# apollo-ctrl.net
KiCad netlist of a schematic drawn in EAGLE
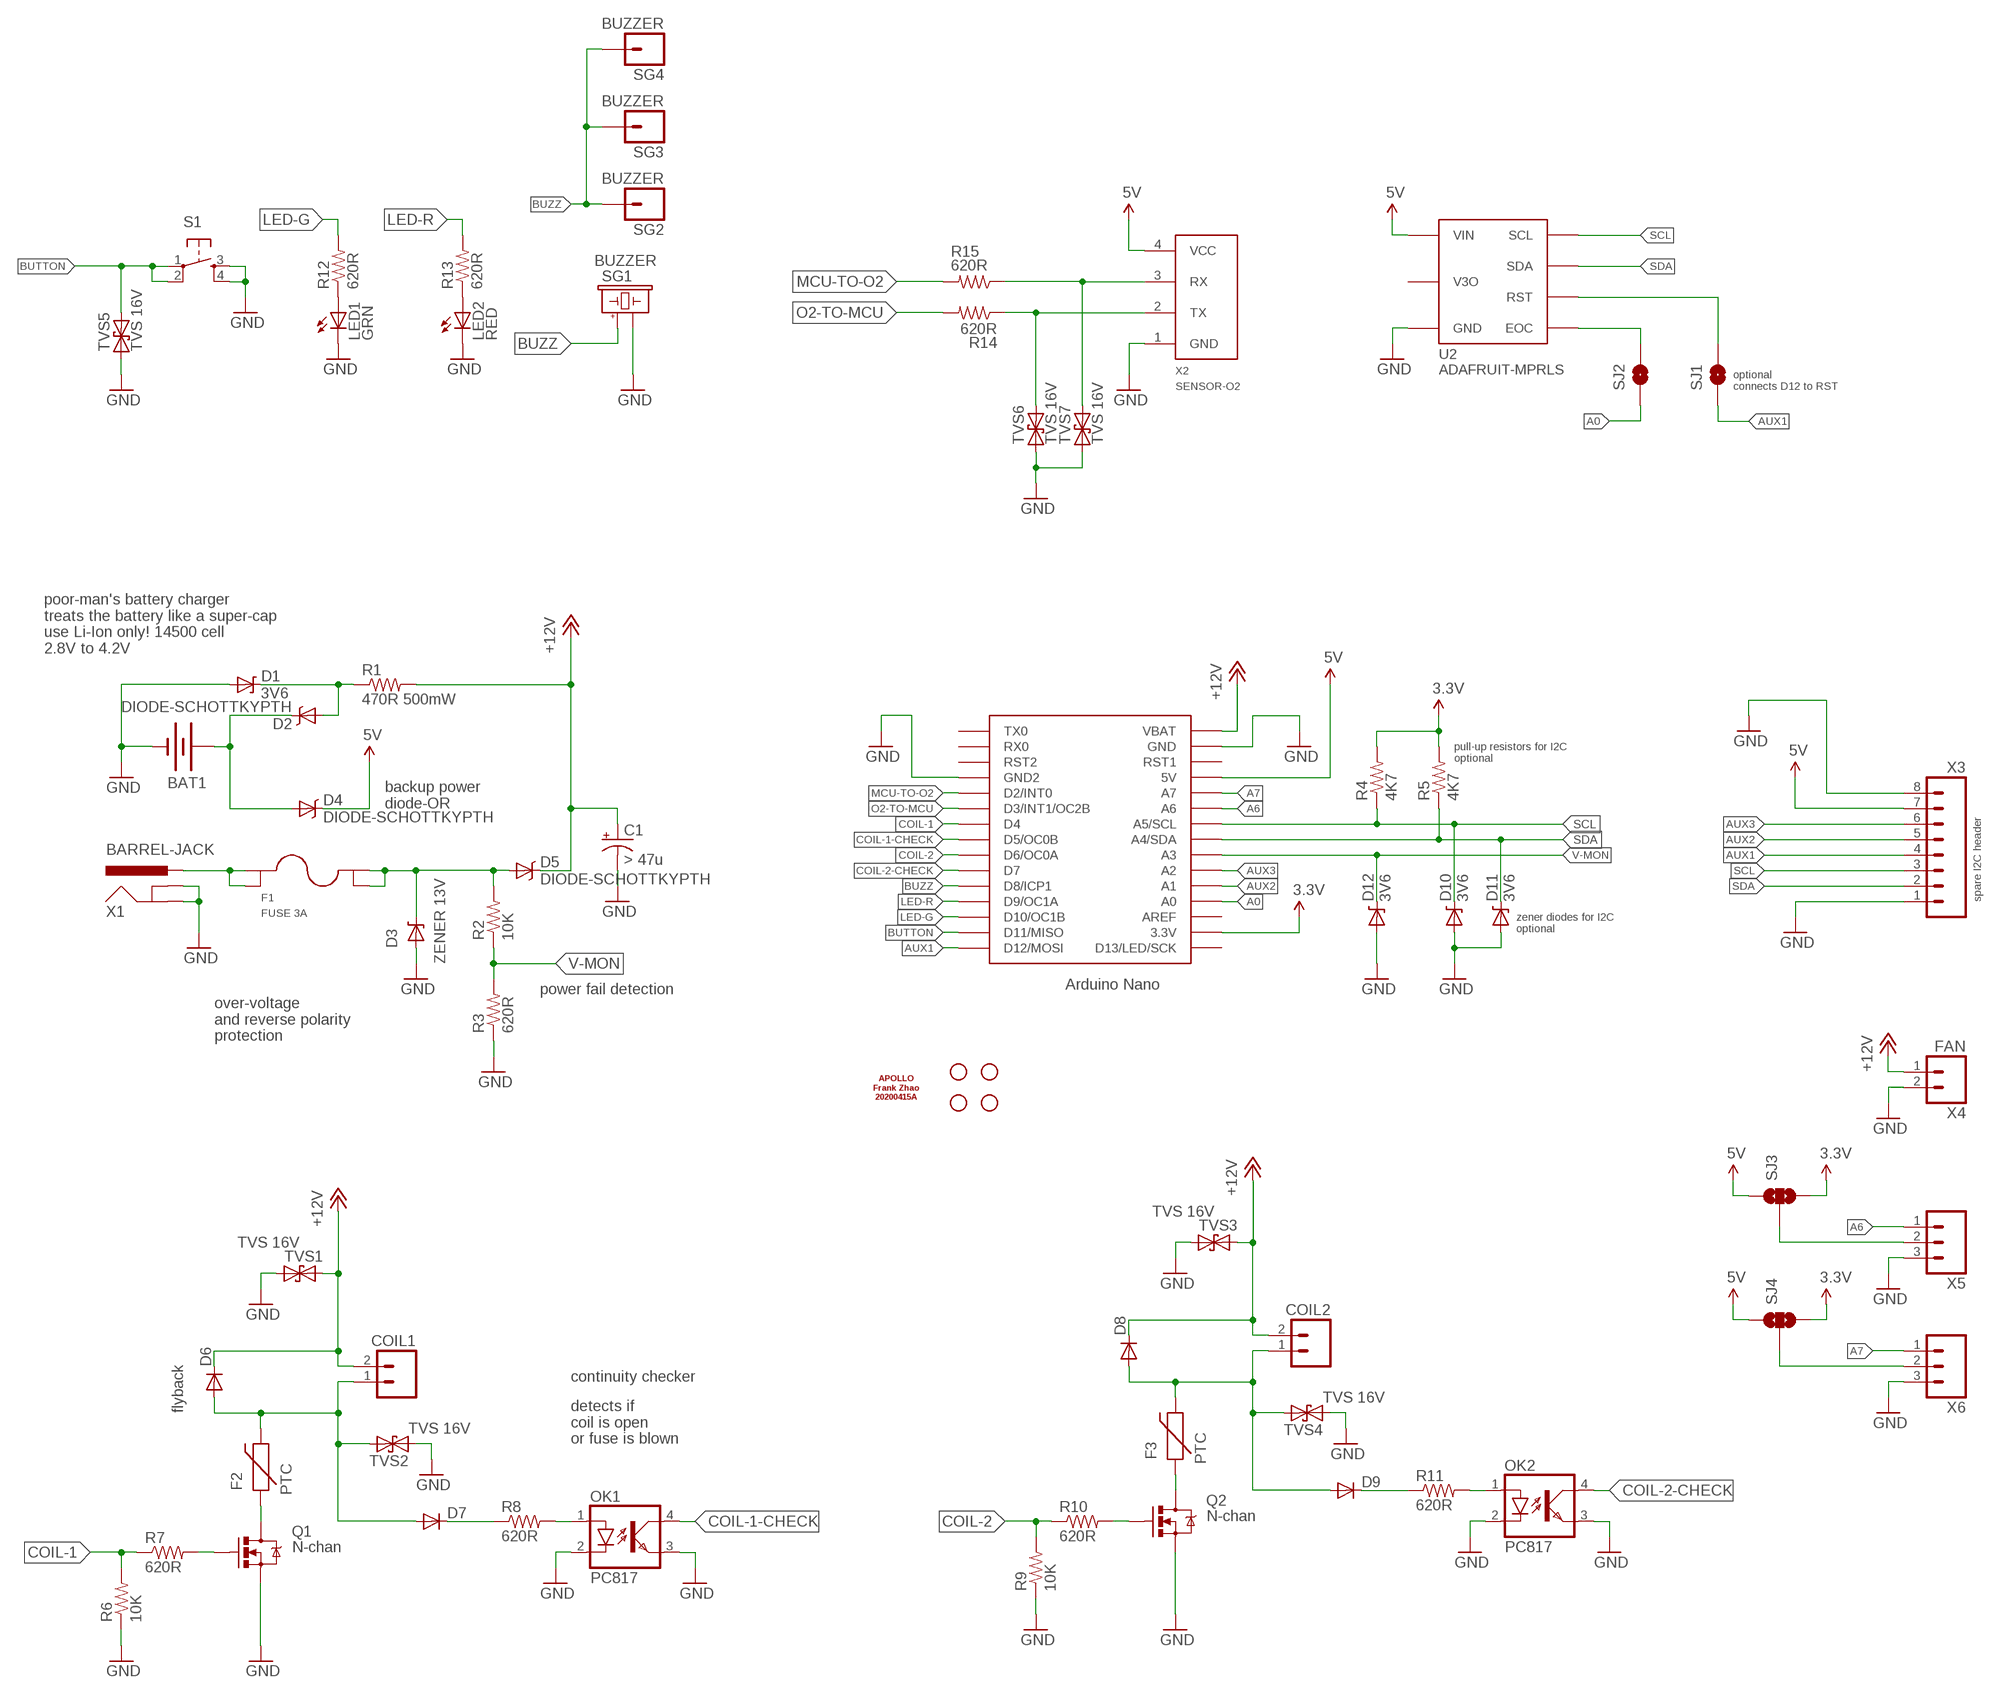
[diagram p0: schematic, sheet 1]

(export (version "E")
  (design (tool "Eeschema 10.0.6"))
  (components
    (comp (ref "BAT1")
      (value "BATTERYAA-KIT")
      (footprint "eagle-import:BATTERY-AA-KIT")
      (libsource (lib "eagle-import") (part "BATTERYAA-KIT"))
    )
    (comp (ref "C1")
      (value "> 47u")
      (footprint "eagle-import:CPOL-RADIAL-1000UF-25V")
      (libsource (lib "eagle-import") (part "CAP_POLPTH4"))
    )
    (comp (ref "COIL1")
      (value "M023.5MM")
      (footprint "eagle-import:SCREWTERMINAL-3.5MM-2")
      (libsource (lib "eagle-import") (part "M023.5MM"))
    )
    (comp (ref "COIL2")
      (value "M023.5MM")
      (footprint "eagle-import:SCREWTERMINAL-3.5MM-2")
      (libsource (lib "eagle-import") (part "M023.5MM"))
    )
    (comp (ref "D1")
      (value "3V6")
      (footprint "eagle-import:DIODE-1N4148")
      (libsource (lib "eagle-import") (part "DIODE-ZENER1N4148"))
    )
    (comp (ref "D2")
      (value "DIODE-SCHOTTKYPTH")
      (footprint "eagle-import:DIODE-1N4001")
      (libsource (lib "eagle-import") (part "DIODE-SCHOTTKYPTH"))
    )
    (comp (ref "D3")
      (value "ZENER 13V")
      (footprint "eagle-import:DO201-15")
      (libsource (lib "eagle-import") (part "DIODE-ZENER-DO201-15"))
    )
    (comp (ref "D4")
      (value "DIODE-SCHOTTKYPTH")
      (footprint "eagle-import:DIODE-1N4001")
      (libsource (lib "eagle-import") (part "DIODE-SCHOTTKYPTH"))
    )
    (comp (ref "D5")
      (value "DIODE-SCHOTTKYPTH")
      (footprint "eagle-import:DIODE-1N4001")
      (libsource (lib "eagle-import") (part "DIODE-SCHOTTKYPTH"))
    )
    (comp (ref "D6")
      (value "DIODE1N4148")
      (footprint "eagle-import:DIODE-1N4148")
      (libsource (lib "eagle-import") (part "DIODE1N4148"))
    )
    (comp (ref "D7")
      (value "DIODE1N4148")
      (footprint "eagle-import:DIODE-1N4148")
      (libsource (lib "eagle-import") (part "DIODE1N4148"))
    )
    (comp (ref "D8")
      (value "DIODE1N4148")
      (footprint "eagle-import:DIODE-1N4148")
      (libsource (lib "eagle-import") (part "DIODE1N4148"))
    )
    (comp (ref "D9")
      (value "DIODE1N4148")
      (footprint "eagle-import:DIODE-1N4148")
      (libsource (lib "eagle-import") (part "DIODE1N4148"))
    )
    (comp (ref "D10")
      (value "3V6")
      (footprint "eagle-import:DIODE-1N4148")
      (libsource (lib "eagle-import") (part "DIODE-ZENER1N4148"))
    )
    (comp (ref "D11")
      (value "3V6")
      (footprint "eagle-import:DIODE-1N4148")
      (libsource (lib "eagle-import") (part "DIODE-ZENER1N4148"))
    )
    (comp (ref "D12")
      (value "3V6")
      (footprint "eagle-import:DIODE-1N4148")
      (libsource (lib "eagle-import") (part "DIODE-ZENER1N4148"))
    )
    (comp (ref "F1")
      (value "FUSE 3A")
      (footprint "eagle-import:FUSE-KEYSTONE-3568")
      (libsource (lib "eagle-import") (part "FUSE-4PIN-KEYSTONE-3568"))
    )
    (comp (ref "F2")
      (value "PTC")
      (footprint "eagle-import:PTC")
      (libsource (lib "eagle-import") (part "PTCPTH"))
    )
    (comp (ref "F3")
      (value "PTC")
      (footprint "eagle-import:PTC")
      (libsource (lib "eagle-import") (part "PTCPTH"))
    )
    (comp (ref "JP1")
      (value "STAND-OFF")
      (footprint "eagle-import:STAND-OFF")
      (libsource (lib "eagle-import") (part "STAND-OFF"))
    )
    (comp (ref "JP2")
      (value "STAND-OFF")
      (footprint "eagle-import:STAND-OFF")
      (libsource (lib "eagle-import") (part "STAND-OFF"))
    )
    (comp (ref "JP3")
      (value "STAND-OFF")
      (footprint "eagle-import:STAND-OFF")
      (libsource (lib "eagle-import") (part "STAND-OFF"))
    )
    (comp (ref "JP4")
      (value "STAND-OFF")
      (footprint "eagle-import:STAND-OFF")
      (libsource (lib "eagle-import") (part "STAND-OFF"))
    )
    (comp (ref "LED1")
      (value "GRN")
      (footprint "eagle-import:LED5MM")
      (libsource (lib "eagle-import") (part "LED5MM"))
    )
    (comp (ref "LED2")
      (value "RED")
      (footprint "eagle-import:LED5MM")
      (libsource (lib "eagle-import") (part "LED5MM"))
    )
    (comp (ref "LOGO1")
      (value "APOLLO-LOGO")
      (footprint "eagle-import:APOLLO-LOGO")
      (libsource (lib "eagle-import") (part "APOLLO-LOGO"))
    )
    (comp (ref "OK1")
      (value "PC817")
      (footprint "eagle-import:DIL04")
      (fields (field (name "MPN") "PC817X4J000F"))
      (libsource (lib "eagle-import") (part "PC817"))
    )
    (comp (ref "OK2")
      (value "PC817")
      (footprint "eagle-import:DIL04")
      (fields (field (name "MPN") "PC817X4J000F"))
      (libsource (lib "eagle-import") (part "PC817"))
    )
    (comp (ref "Q1")
      (value "N-chan")
      (footprint "eagle-import:TO220V")
      (libsource (lib "eagle-import") (part "MOSFET-NCHANNELPTH2"))
    )
    (comp (ref "Q2")
      (value "N-chan")
      (footprint "eagle-import:TO220V")
      (libsource (lib "eagle-import") (part "MOSFET-NCHANNELPTH2"))
    )
    (comp (ref "R1")
      (value "470R 500mW")
      (footprint "eagle-import:AXIAL-0.5")
      (libsource (lib "eagle-import") (part "RESISTORPTH-1/2W"))
    )
    (comp (ref "R2")
      (value "10K")
      (footprint "eagle-import:AXIAL-0.4")
      (libsource (lib "eagle-import") (part "RESISTORPTH-1/4W"))
    )
    (comp (ref "R3")
      (value "620R")
      (footprint "eagle-import:AXIAL-0.4")
      (libsource (lib "eagle-import") (part "RESISTORPTH-1/4W"))
    )
    (comp (ref "R4")
      (value "4K7")
      (footprint "eagle-import:AXIAL-0.4")
      (libsource (lib "eagle-import") (part "RESISTORPTH-1/4W"))
    )
    (comp (ref "R5")
      (value "4K7")
      (footprint "eagle-import:AXIAL-0.4")
      (libsource (lib "eagle-import") (part "RESISTORPTH-1/4W"))
    )
    (comp (ref "R6")
      (value "10K")
      (footprint "eagle-import:AXIAL-0.4")
      (libsource (lib "eagle-import") (part "RESISTORPTH-1/4W"))
    )
    (comp (ref "R7")
      (value "620R")
      (footprint "eagle-import:AXIAL-0.4")
      (libsource (lib "eagle-import") (part "RESISTORPTH-1/4W"))
    )
    (comp (ref "R8")
      (value "620R")
      (footprint "eagle-import:AXIAL-0.4")
      (libsource (lib "eagle-import") (part "RESISTORPTH-1/4W"))
    )
    (comp (ref "R9")
      (value "10K")
      (footprint "eagle-import:AXIAL-0.4")
      (libsource (lib "eagle-import") (part "RESISTORPTH-1/4W"))
    )
    (comp (ref "R10")
      (value "620R")
      (footprint "eagle-import:AXIAL-0.4")
      (libsource (lib "eagle-import") (part "RESISTORPTH-1/4W"))
    )
    (comp (ref "R11")
      (value "620R")
      (footprint "eagle-import:AXIAL-0.4")
      (libsource (lib "eagle-import") (part "RESISTORPTH-1/4W"))
    )
    (comp (ref "R12")
      (value "620R")
      (footprint "eagle-import:AXIAL-0.4")
      (libsource (lib "eagle-import") (part "RESISTORPTH-1/4W"))
    )
    (comp (ref "R13")
      (value "620R")
      (footprint "eagle-import:AXIAL-0.4")
      (libsource (lib "eagle-import") (part "RESISTORPTH-1/4W"))
    )
    (comp (ref "R14")
      (value "620R")
      (footprint "eagle-import:AXIAL-0.4")
      (libsource (lib "eagle-import") (part "RESISTORPTH-1/4W"))
    )
    (comp (ref "R15")
      (value "620R")
      (footprint "eagle-import:AXIAL-0.4")
      (libsource (lib "eagle-import") (part "RESISTORPTH-1/4W"))
    )
    (comp (ref "S1")
      (value "TAC_SWITCHPTH")
      (footprint "eagle-import:TACTILE-PTH")
      (libsource (lib "eagle-import") (part "TAC_SWITCHPTH"))
    )
    (comp (ref "SG1")
      (value "BUZZER")
      (footprint "eagle-import:BUZZER-AI-3035")
      (libsource (lib "eagle-import") (part "BUZZER-POL-AI-3035"))
    )
    (comp (ref "SG2")
      (value "BUZZER")
      (footprint "eagle-import:1X01NS")
      (libsource (lib "eagle-import") (part "M01-TH-NS"))
    )
    (comp (ref "SG3")
      (value "BUZZER")
      (footprint "eagle-import:1X01NS")
      (libsource (lib "eagle-import") (part "M01-TH-NS"))
    )
    (comp (ref "SG4")
      (value "BUZZER")
      (footprint "eagle-import:1X01NS")
      (libsource (lib "eagle-import") (part "M01-TH-NS"))
    )
    (comp (ref "SJ1")
      (value "SOLDERJUMPERNO")
      (footprint "eagle-import:SJ_2S-NO")
      (libsource (lib "eagle-import") (part "SOLDERJUMPERNO"))
    )
    (comp (ref "SJ2")
      (value "SOLDERJUMPERNO")
      (footprint "eagle-import:SJ_2S-NO")
      (libsource (lib "eagle-import") (part "SOLDERJUMPERNO"))
    )
    (comp (ref "SJ3")
      (value "SOLDERJUMPER_2WAYS")
      (footprint "eagle-import:SJ_3")
      (libsource (lib "eagle-import") (part "SOLDERJUMPER_2WAYS"))
    )
    (comp (ref "SJ4")
      (value "SOLDERJUMPER_2WAYS")
      (footprint "eagle-import:SJ_3")
      (libsource (lib "eagle-import") (part "SOLDERJUMPER_2WAYS"))
    )
    (comp (ref "TVS1")
      (value "TVS 16V")
      (footprint "eagle-import:DIODE-1N4148")
      (libsource (lib "eagle-import") (part "TVS1N4148"))
    )
    (comp (ref "TVS2")
      (value "TVS 16V")
      (footprint "eagle-import:DIODE-1N4148")
      (libsource (lib "eagle-import") (part "TVS1N4148"))
    )
    (comp (ref "TVS3")
      (value "TVS 16V")
      (footprint "eagle-import:DIODE-1N4148")
      (libsource (lib "eagle-import") (part "TVS1N4148"))
    )
    (comp (ref "TVS4")
      (value "TVS 16V")
      (footprint "eagle-import:DIODE-1N4148")
      (libsource (lib "eagle-import") (part "TVS1N4148"))
    )
    (comp (ref "TVS5")
      (value "TVS 16V")
      (footprint "eagle-import:DIODE-1N4148")
      (libsource (lib "eagle-import") (part "TVS1N4148"))
    )
    (comp (ref "TVS6")
      (value "TVS 16V")
      (footprint "eagle-import:DIODE-1N4148")
      (libsource (lib "eagle-import") (part "TVS1N4148"))
    )
    (comp (ref "TVS7")
      (value "TVS 16V")
      (footprint "eagle-import:DIODE-1N4148")
      (libsource (lib "eagle-import") (part "TVS1N4148"))
    )
    (comp (ref "U1")
      (value "NANO")
      (footprint "eagle-import:NANO")
      (libsource (lib "eagle-import") (part "NANO"))
    )
    (comp (ref "U2")
      (value "ADAFRUIT-MPRLS")
      (footprint "eagle-import:ADAFRUIT-MPRLS")
      (libsource (lib "eagle-import") (part "ADAFRUIT-MPRLS-W-HOLES"))
    )
    (comp (ref "X1")
      (value "BARREL-JACK")
      (footprint "eagle-import:POWER_JACK_PTH")
      (libsource (lib "eagle-import") (part "POWER_JACKPTH"))
    )
    (comp (ref "X2")
      (value "SENSOR-O2")
      (footprint "eagle-import:JST-PH-4-VERT")
      (libsource (lib "eagle-import") (part "SENSOR-O2-JST-VERT"))
    )
    (comp (ref "X3")
      (value "M081X08")
      (footprint "eagle-import:1X08")
      (libsource (lib "eagle-import") (part "M081X08"))
    )
    (comp (ref "X4")
      (value "FAN")
      (footprint "eagle-import:1X02")
      (libsource (lib "eagle-import") (part "M02PTH"))
    )
    (comp (ref "X5")
      (value "M03PTH")
      (footprint "eagle-import:1X03")
      (libsource (lib "eagle-import") (part "M03PTH"))
    )
    (comp (ref "X6")
      (value "M03PTH")
      (footprint "eagle-import:1X03")
      (libsource (lib "eagle-import") (part "M03PTH"))
    )
  )
  (nets
    (net (code "1") (name "+12V") (class "Default")
      (node (ref "C1") (pin "1") (pinfunction "+_1") (pintype "passive"))
      (node (ref "COIL1") (pin "2") (pinfunction "2_2") (pintype "passive"))
      (node (ref "COIL2") (pin "2") (pinfunction "2_2") (pintype "passive"))
      (node (ref "D5") (pin "C") (pinfunction "C_C") (pintype "passive"))
      (node (ref "D6") (pin "C") (pinfunction "C_C") (pintype "passive"))
      (node (ref "D8") (pin "C") (pinfunction "C_C") (pintype "passive"))
      (node (ref "R1") (pin "P$2") (pinfunction "2_P$2") (pintype "passive"))
      (node (ref "TVS1") (pin "C") (pinfunction "C_C") (pintype "passive"))
      (node (ref "TVS3") (pin "C") (pinfunction "C_C") (pintype "passive"))
      (node (ref "U1") (pin "RAW") (pinfunction "VBAT_RAW") (pintype "bidirectional"))
      (node (ref "X4") (pin "1") (pinfunction "1_1") (pintype "passive"))
    )
    (net (code "2") (name "3.3V") (class "Default")
      (node (ref "R4") (pin "P$2") (pinfunction "2_P$2") (pintype "passive"))
      (node (ref "R5") (pin "P$2") (pinfunction "2_P$2") (pintype "passive"))
      (node (ref "SJ3") (pin "3") (pinfunction "3_3") (pintype "passive"))
      (node (ref "SJ4") (pin "3") (pinfunction "3_3") (pintype "passive"))
      (node (ref "U1") (pin "3.3V") (pinfunction "3.3V_3.3V") (pintype "bidirectional"))
    )
    (net (code "3") (name "5V") (class "Default")
      (node (ref "D4") (pin "C") (pinfunction "C_C") (pintype "passive"))
      (node (ref "SJ3") (pin "1") (pinfunction "1_1") (pintype "passive"))
      (node (ref "SJ4") (pin "1") (pinfunction "1_1") (pintype "passive"))
      (node (ref "U1") (pin "5V") (pinfunction "5V_5V") (pintype "bidirectional"))
      (node (ref "U2") (pin "VIN") (pinfunction "VIN_VIN") (pintype "input"))
      (node (ref "X2") (pin "4") (pinfunction "VCC_4") (pintype "input"))
      (node (ref "X3") (pin "7") (pinfunction "7_7") (pintype "passive"))
    )
    (net (code "4") (name "A0") (class "Default")
      (node (ref "SJ2") (pin "1") (pinfunction "1_1") (pintype "passive"))
      (node (ref "U1") (pin "A0") (pinfunction "A0_A0") (pintype "bidirectional"))
    )
    (net (code "5") (name "A6") (class "Default")
      (node (ref "U1") (pin "A6") (pinfunction "A6_A6") (pintype "bidirectional"))
      (node (ref "X5") (pin "1") (pinfunction "1_1") (pintype "passive"))
    )
    (net (code "6") (name "A7") (class "Default")
      (node (ref "U1") (pin "A7") (pinfunction "A7_A7") (pintype "bidirectional"))
      (node (ref "X6") (pin "1") (pinfunction "1_1") (pintype "passive"))
    )
    (net (code "7") (name "AUX1") (class "Default")
      (node (ref "SJ1") (pin "1") (pinfunction "1_1") (pintype "passive"))
      (node (ref "U1") (pin "D12") (pinfunction "D12/MOSI_D12") (pintype "bidirectional"))
      (node (ref "X3") (pin "4") (pinfunction "4_4") (pintype "passive"))
    )
    (net (code "8") (name "AUX2") (class "Default")
      (node (ref "U1") (pin "A1") (pinfunction "A1_A1") (pintype "bidirectional"))
      (node (ref "X3") (pin "5") (pinfunction "5_5") (pintype "passive"))
    )
    (net (code "9") (name "AUX3") (class "Default")
      (node (ref "U1") (pin "A2") (pinfunction "A2_A2") (pintype "bidirectional"))
      (node (ref "X3") (pin "6") (pinfunction "6_6") (pintype "passive"))
    )
    (net (code "10") (name "BUTTON") (class "Default")
      (node (ref "S1") (pin "1") (pinfunction "1_1") (pintype "passive"))
      (node (ref "S1") (pin "2") (pinfunction "2_2") (pintype "passive"))
      (node (ref "TVS5") (pin "C") (pinfunction "C_C") (pintype "passive"))
      (node (ref "U1") (pin "D11") (pinfunction "D11/MISO_D11") (pintype "bidirectional"))
    )
    (net (code "11") (name "BUZZ") (class "Default")
      (node (ref "SG1") (pin "P") (pinfunction "P_P") (pintype "passive"))
      (node (ref "SG2") (pin "1") (pinfunction "1_1") (pintype "passive"))
      (node (ref "SG3") (pin "1") (pinfunction "1_1") (pintype "passive"))
      (node (ref "SG4") (pin "1") (pinfunction "1_1") (pintype "passive"))
      (node (ref "U1") (pin "D8") (pinfunction "D8/ICP1_D8") (pintype "bidirectional"))
    )
    (net (code "12") (name "COIL-1") (class "Default")
      (node (ref "R6") (pin "P$2") (pinfunction "2_P$2") (pintype "passive"))
      (node (ref "R7") (pin "P$1") (pinfunction "1_P$1") (pintype "passive"))
      (node (ref "U1") (pin "D4") (pinfunction "D4_D4") (pintype "bidirectional"))
    )
    (net (code "13") (name "COIL-1-CHECK") (class "Default")
      (node (ref "OK1") (pin "4") (pinfunction "COL_4") (pintype "passive"))
      (node (ref "U1") (pin "D5") (pinfunction "D5/OC0B_D5") (pintype "bidirectional"))
    )
    (net (code "14") (name "COIL-2") (class "Default")
      (node (ref "R10") (pin "P$1") (pinfunction "1_P$1") (pintype "passive"))
      (node (ref "R9") (pin "P$2") (pinfunction "2_P$2") (pintype "passive"))
      (node (ref "U1") (pin "D6") (pinfunction "D6/OC0A_D6") (pintype "bidirectional"))
    )
    (net (code "15") (name "COIL-2-CHECK") (class "Default")
      (node (ref "OK2") (pin "4") (pinfunction "COL_4") (pintype "passive"))
      (node (ref "U1") (pin "D7") (pinfunction "D7_D7") (pintype "bidirectional"))
    )
    (net (code "16") (name "GND") (class "Default")
      (node (ref "BAT1") (pin "GND@1") (pinfunction "-_GND@1") (pintype "power_in"))
      (node (ref "C1") (pin "2") (pinfunction "-_2") (pintype "passive"))
      (node (ref "D1") (pin "A") (pinfunction "A_A") (pintype "passive"))
      (node (ref "D10") (pin "A") (pinfunction "A_A") (pintype "passive"))
      (node (ref "D11") (pin "A") (pinfunction "A_A") (pintype "passive"))
      (node (ref "D12") (pin "A") (pinfunction "A_A") (pintype "passive"))
      (node (ref "D3") (pin "A") (pinfunction "A_A") (pintype "passive"))
      (node (ref "LED1") (pin "K") (pinfunction "C_K") (pintype "passive"))
      (node (ref "LED2") (pin "K") (pinfunction "C_K") (pintype "passive"))
      (node (ref "OK1") (pin "2") (pinfunction "C_2") (pintype "passive"))
      (node (ref "OK1") (pin "3") (pinfunction "EMIT_3") (pintype "passive"))
      (node (ref "OK2") (pin "2") (pinfunction "C_2") (pintype "passive"))
      (node (ref "OK2") (pin "3") (pinfunction "EMIT_3") (pintype "passive"))
      (node (ref "Q1") (pin "3") (pinfunction "S_3") (pintype "passive"))
      (node (ref "Q2") (pin "3") (pinfunction "S_3") (pintype "passive"))
      (node (ref "R3") (pin "P$1") (pinfunction "1_P$1") (pintype "passive"))
      (node (ref "R6") (pin "P$1") (pinfunction "1_P$1") (pintype "passive"))
      (node (ref "R9") (pin "P$1") (pinfunction "1_P$1") (pintype "passive"))
      (node (ref "S1") (pin "3") (pinfunction "3_3") (pintype "passive"))
      (node (ref "S1") (pin "4") (pinfunction "4_4") (pintype "passive"))
      (node (ref "SG1") (pin "N") (pinfunction "N_N") (pintype "passive"))
      (node (ref "TVS1") (pin "A") (pinfunction "A_A") (pintype "passive"))
      (node (ref "TVS2") (pin "A") (pinfunction "A_A") (pintype "passive"))
      (node (ref "TVS3") (pin "A") (pinfunction "A_A") (pintype "passive"))
      (node (ref "TVS4") (pin "A") (pinfunction "A_A") (pintype "passive"))
      (node (ref "TVS5") (pin "A") (pinfunction "A_A") (pintype "passive"))
      (node (ref "TVS6") (pin "A") (pinfunction "A_A") (pintype "passive"))
      (node (ref "TVS7") (pin "A") (pinfunction "A_A") (pintype "passive"))
      (node (ref "U1") (pin "GND") (pinfunction "GND_GND") (pintype "bidirectional"))
      (node (ref "U1") (pin "GND1") (pinfunction "GND2_GND1") (pintype "bidirectional"))
      (node (ref "U2") (pin "GND") (pinfunction "GND_GND") (pintype "input"))
      (node (ref "X1") (pin "GND") (pinfunction "GND_GND") (pintype "bidirectional"))
      (node (ref "X1") (pin "GNDBREAK") (pinfunction "GNDBREAK_GNDBREAK") (pintype "bidirectional"))
      (node (ref "X2") (pin "1") (pinfunction "GND_1") (pintype "input"))
      (node (ref "X3") (pin "1") (pinfunction "1_1") (pintype "passive"))
      (node (ref "X3") (pin "8") (pinfunction "8_8") (pintype "passive"))
      (node (ref "X4") (pin "2") (pinfunction "2_2") (pintype "passive"))
      (node (ref "X5") (pin "3") (pinfunction "3_3") (pintype "passive"))
      (node (ref "X6") (pin "3") (pinfunction "3_3") (pintype "passive"))
    )
    (net (code "17") (name "LED-G") (class "Default")
      (node (ref "R12") (pin "P$2") (pinfunction "2_P$2") (pintype "passive"))
      (node (ref "U1") (pin "D10") (pinfunction "D10/OC1B_D10") (pintype "bidirectional"))
    )
    (net (code "18") (name "LED-R") (class "Default")
      (node (ref "R13") (pin "P$2") (pinfunction "2_P$2") (pintype "passive"))
      (node (ref "U1") (pin "D9") (pinfunction "D9/OC1A_D9") (pintype "bidirectional"))
    )
    (net (code "19") (name "MCU-TO-O2") (class "Default")
      (node (ref "R15") (pin "P$2") (pinfunction "2_P$2") (pintype "passive"))
      (node (ref "U1") (pin "D2") (pinfunction "D2/INT0_D2") (pintype "bidirectional"))
    )
    (net (code "20") (name "Net-(BAT1-+)") (class "Default")
      (node (ref "BAT1") (pin "PWR@1") (pinfunction "+_PWR@1") (pintype "power_in"))
      (node (ref "D2") (pin "C") (pinfunction "C_C") (pintype "passive"))
      (node (ref "D4") (pin "A") (pinfunction "A_A") (pintype "passive"))
    )
    (net (code "21") (name "Net-(COIL1-Pad1)") (class "Default")
      (node (ref "COIL1") (pin "1") (pinfunction "1_1") (pintype "passive"))
      (node (ref "D6") (pin "A") (pinfunction "A_A") (pintype "passive"))
      (node (ref "D7") (pin "A") (pinfunction "A_A") (pintype "passive"))
      (node (ref "F2") (pin "2") (pinfunction "2_2") (pintype "bidirectional"))
      (node (ref "TVS2") (pin "C") (pinfunction "C_C") (pintype "passive"))
    )
    (net (code "22") (name "Net-(COIL2-Pad1)") (class "Default")
      (node (ref "COIL2") (pin "1") (pinfunction "1_1") (pintype "passive"))
      (node (ref "D8") (pin "A") (pinfunction "A_A") (pintype "passive"))
      (node (ref "D9") (pin "A") (pinfunction "A_A") (pintype "passive"))
      (node (ref "F3") (pin "2") (pinfunction "2_2") (pintype "bidirectional"))
      (node (ref "TVS4") (pin "C") (pinfunction "C_C") (pintype "passive"))
    )
    (net (code "23") (name "Net-(F1-Pad1A)") (class "Default")
      (node (ref "F1") (pin "1A") (pinfunction "1A_1A") (pintype "bidirectional"))
      (node (ref "F1") (pin "1B") (pinfunction "1B_1B") (pintype "bidirectional"))
      (node (ref "X1") (pin "PWR") (pinfunction "PWR_PWR") (pintype "bidirectional"))
    )
    (net (code "24") (name "Net-(OK1-A)") (class "Default")
      (node (ref "OK1") (pin "1") (pinfunction "A_1") (pintype "passive"))
      (node (ref "R8") (pin "P$2") (pinfunction "2_P$2") (pintype "passive"))
    )
    (net (code "25") (name "Net-(OK2-A)") (class "Default")
      (node (ref "OK2") (pin "1") (pinfunction "A_1") (pintype "passive"))
      (node (ref "R11") (pin "P$2") (pinfunction "2_P$2") (pintype "passive"))
    )
    (net (code "26") (name "Net-(Q1-D)") (class "Default")
      (node (ref "F2") (pin "1") (pinfunction "1_1") (pintype "bidirectional"))
      (node (ref "Q1") (pin "2") (pinfunction "D_2") (pintype "passive"))
    )
    (net (code "27") (name "Net-(Q1-G)") (class "Default")
      (node (ref "Q1") (pin "1") (pinfunction "G_1") (pintype "passive"))
      (node (ref "R7") (pin "P$2") (pinfunction "2_P$2") (pintype "passive"))
    )
    (net (code "28") (name "Net-(Q2-D)") (class "Default")
      (node (ref "F3") (pin "1") (pinfunction "1_1") (pintype "bidirectional"))
      (node (ref "Q2") (pin "2") (pinfunction "D_2") (pintype "passive"))
    )
    (net (code "29") (name "Net-(Q2-G)") (class "Default")
      (node (ref "Q2") (pin "1") (pinfunction "G_1") (pintype "passive"))
      (node (ref "R10") (pin "P$2") (pinfunction "2_P$2") (pintype "passive"))
    )
    (net (code "30") (name "Net-(R1-1)") (class "Default")
      (node (ref "D1") (pin "C") (pinfunction "C_C") (pintype "passive"))
      (node (ref "D2") (pin "A") (pinfunction "A_A") (pintype "passive"))
      (node (ref "R1") (pin "P$1") (pinfunction "1_P$1") (pintype "passive"))
    )
    (net (code "31") (name "Net-(R2-2)") (class "Default")
      (node (ref "D3") (pin "C") (pinfunction "C_C") (pintype "passive"))
      (node (ref "D5") (pin "A") (pinfunction "A_A") (pintype "passive"))
      (node (ref "F1") (pin "2A") (pinfunction "2A_2A") (pintype "bidirectional"))
      (node (ref "F1") (pin "2B") (pinfunction "2B_2B") (pintype "bidirectional"))
      (node (ref "R2") (pin "P$2") (pinfunction "2_P$2") (pintype "passive"))
    )
    (net (code "32") (name "Net-(R8-1)") (class "Default")
      (node (ref "D7") (pin "C") (pinfunction "C_C") (pintype "passive"))
      (node (ref "R8") (pin "P$1") (pinfunction "1_P$1") (pintype "passive"))
    )
    (net (code "33") (name "Net-(R11-1)") (class "Default")
      (node (ref "D9") (pin "C") (pinfunction "C_C") (pintype "passive"))
      (node (ref "R11") (pin "P$1") (pinfunction "1_P$1") (pintype "passive"))
    )
    (net (code "34") (name "Net-(R12-1)") (class "Default")
      (node (ref "LED1") (pin "A") (pinfunction "A_A") (pintype "passive"))
      (node (ref "R12") (pin "P$1") (pinfunction "1_P$1") (pintype "passive"))
    )
    (net (code "35") (name "Net-(R13-1)") (class "Default")
      (node (ref "LED2") (pin "A") (pinfunction "A_A") (pintype "passive"))
      (node (ref "R13") (pin "P$1") (pinfunction "1_P$1") (pintype "passive"))
    )
    (net (code "36") (name "Net-(R14-1)") (class "Default")
      (node (ref "R14") (pin "P$1") (pinfunction "1_P$1") (pintype "passive"))
      (node (ref "TVS6") (pin "C") (pinfunction "C_C") (pintype "passive"))
      (node (ref "X2") (pin "2") (pinfunction "TX_2") (pintype "bidirectional"))
    )
    (net (code "37") (name "Net-(R15-1)") (class "Default")
      (node (ref "R15") (pin "P$1") (pinfunction "1_P$1") (pintype "passive"))
      (node (ref "TVS7") (pin "C") (pinfunction "C_C") (pintype "passive"))
      (node (ref "X2") (pin "3") (pinfunction "RX_3") (pintype "bidirectional"))
    )
    (net (code "38") (name "Net-(SJ1-Pad2)") (class "Default")
      (node (ref "SJ1") (pin "2") (pinfunction "2_2") (pintype "passive"))
      (node (ref "U2") (pin "RST") (pinfunction "RST_RST") (pintype "input"))
    )
    (net (code "39") (name "Net-(SJ2-Pad2)") (class "Default")
      (node (ref "SJ2") (pin "2") (pinfunction "2_2") (pintype "passive"))
      (node (ref "U2") (pin "EOC") (pinfunction "EOC_EOC") (pintype "output"))
    )
    (net (code "40") (name "Net-(SJ3-Pad2)") (class "Default")
      (node (ref "SJ3") (pin "2") (pinfunction "2_2") (pintype "passive"))
      (node (ref "X5") (pin "2") (pinfunction "2_2") (pintype "passive"))
    )
    (net (code "41") (name "Net-(SJ4-Pad2)") (class "Default")
      (node (ref "SJ4") (pin "2") (pinfunction "2_2") (pintype "passive"))
      (node (ref "X6") (pin "2") (pinfunction "2_2") (pintype "passive"))
    )
    (net (code "42") (name "O2-TO-MCU") (class "Default")
      (node (ref "R14") (pin "P$2") (pinfunction "2_P$2") (pintype "passive"))
      (node (ref "U1") (pin "D3") (pinfunction "D3/INT1/OC2B_D3") (pintype "bidirectional"))
    )
    (net (code "43") (name "SCL") (class "Default")
      (node (ref "D10") (pin "C") (pinfunction "C_C") (pintype "passive"))
      (node (ref "R4") (pin "P$1") (pinfunction "1_P$1") (pintype "passive"))
      (node (ref "U1") (pin "A5") (pinfunction "A5/SCL_A5") (pintype "bidirectional"))
      (node (ref "U2") (pin "SCL") (pinfunction "SCL_SCL") (pintype "bidirectional"))
      (node (ref "X3") (pin "3") (pinfunction "3_3") (pintype "passive"))
    )
    (net (code "44") (name "SDA") (class "Default")
      (node (ref "D11") (pin "C") (pinfunction "C_C") (pintype "passive"))
      (node (ref "R5") (pin "P$1") (pinfunction "1_P$1") (pintype "passive"))
      (node (ref "U1") (pin "A4") (pinfunction "A4/SDA_A4") (pintype "bidirectional"))
      (node (ref "U2") (pin "SDA") (pinfunction "SDA_SDA") (pintype "bidirectional"))
      (node (ref "X3") (pin "2") (pinfunction "2_2") (pintype "passive"))
    )
    (net (code "45") (name "V-MON") (class "Default")
      (node (ref "D12") (pin "C") (pinfunction "C_C") (pintype "passive"))
      (node (ref "R2") (pin "P$1") (pinfunction "1_P$1") (pintype "passive"))
      (node (ref "R3") (pin "P$2") (pinfunction "2_P$2") (pintype "passive"))
      (node (ref "U1") (pin "A3") (pinfunction "A3_A3") (pintype "bidirectional"))
    )
    (net (code "46") (name "unconnected-(U1-D13{slash}LED{slash}SCK-PadD13)") (class "Default")
      (node (ref "U1") (pin "D13") (pinfunction "D13/LED/SCK_D13") (pintype "bidirectional"))
    )
    (net (code "47") (name "unconnected-(U1-PadAREF)") (class "Default")
      (node (ref "U1") (pin "AREF") (pinfunction "AREF_AREF") (pintype "bidirectional"))
    )
    (net (code "48") (name "unconnected-(U1-PadRX0)") (class "Default")
      (node (ref "U1") (pin "RX0") (pinfunction "RX0_RX0") (pintype "bidirectional"))
    )
    (net (code "49") (name "unconnected-(U1-PadTX0)") (class "Default")
      (node (ref "U1") (pin "TX0") (pinfunction "TX0_TX0") (pintype "bidirectional"))
    )
    (net (code "50") (name "unconnected-(U1-RST1-PadRST)") (class "Default")
      (node (ref "U1") (pin "RST") (pinfunction "RST1_RST") (pintype "bidirectional"))
    )
    (net (code "51") (name "unconnected-(U1-RST2-PadRST1)") (class "Default")
      (node (ref "U1") (pin "RST1") (pinfunction "RST2_RST1") (pintype "bidirectional"))
    )
    (net (code "52") (name "unconnected-(U2-PadV3O)") (class "Default")
      (node (ref "U2") (pin "V3O") (pinfunction "V3O_V3O") (pintype "bidirectional"))
    )
  )
)
